# electronicload.net
KiCad netlist of a schematic drawn in EAGLE
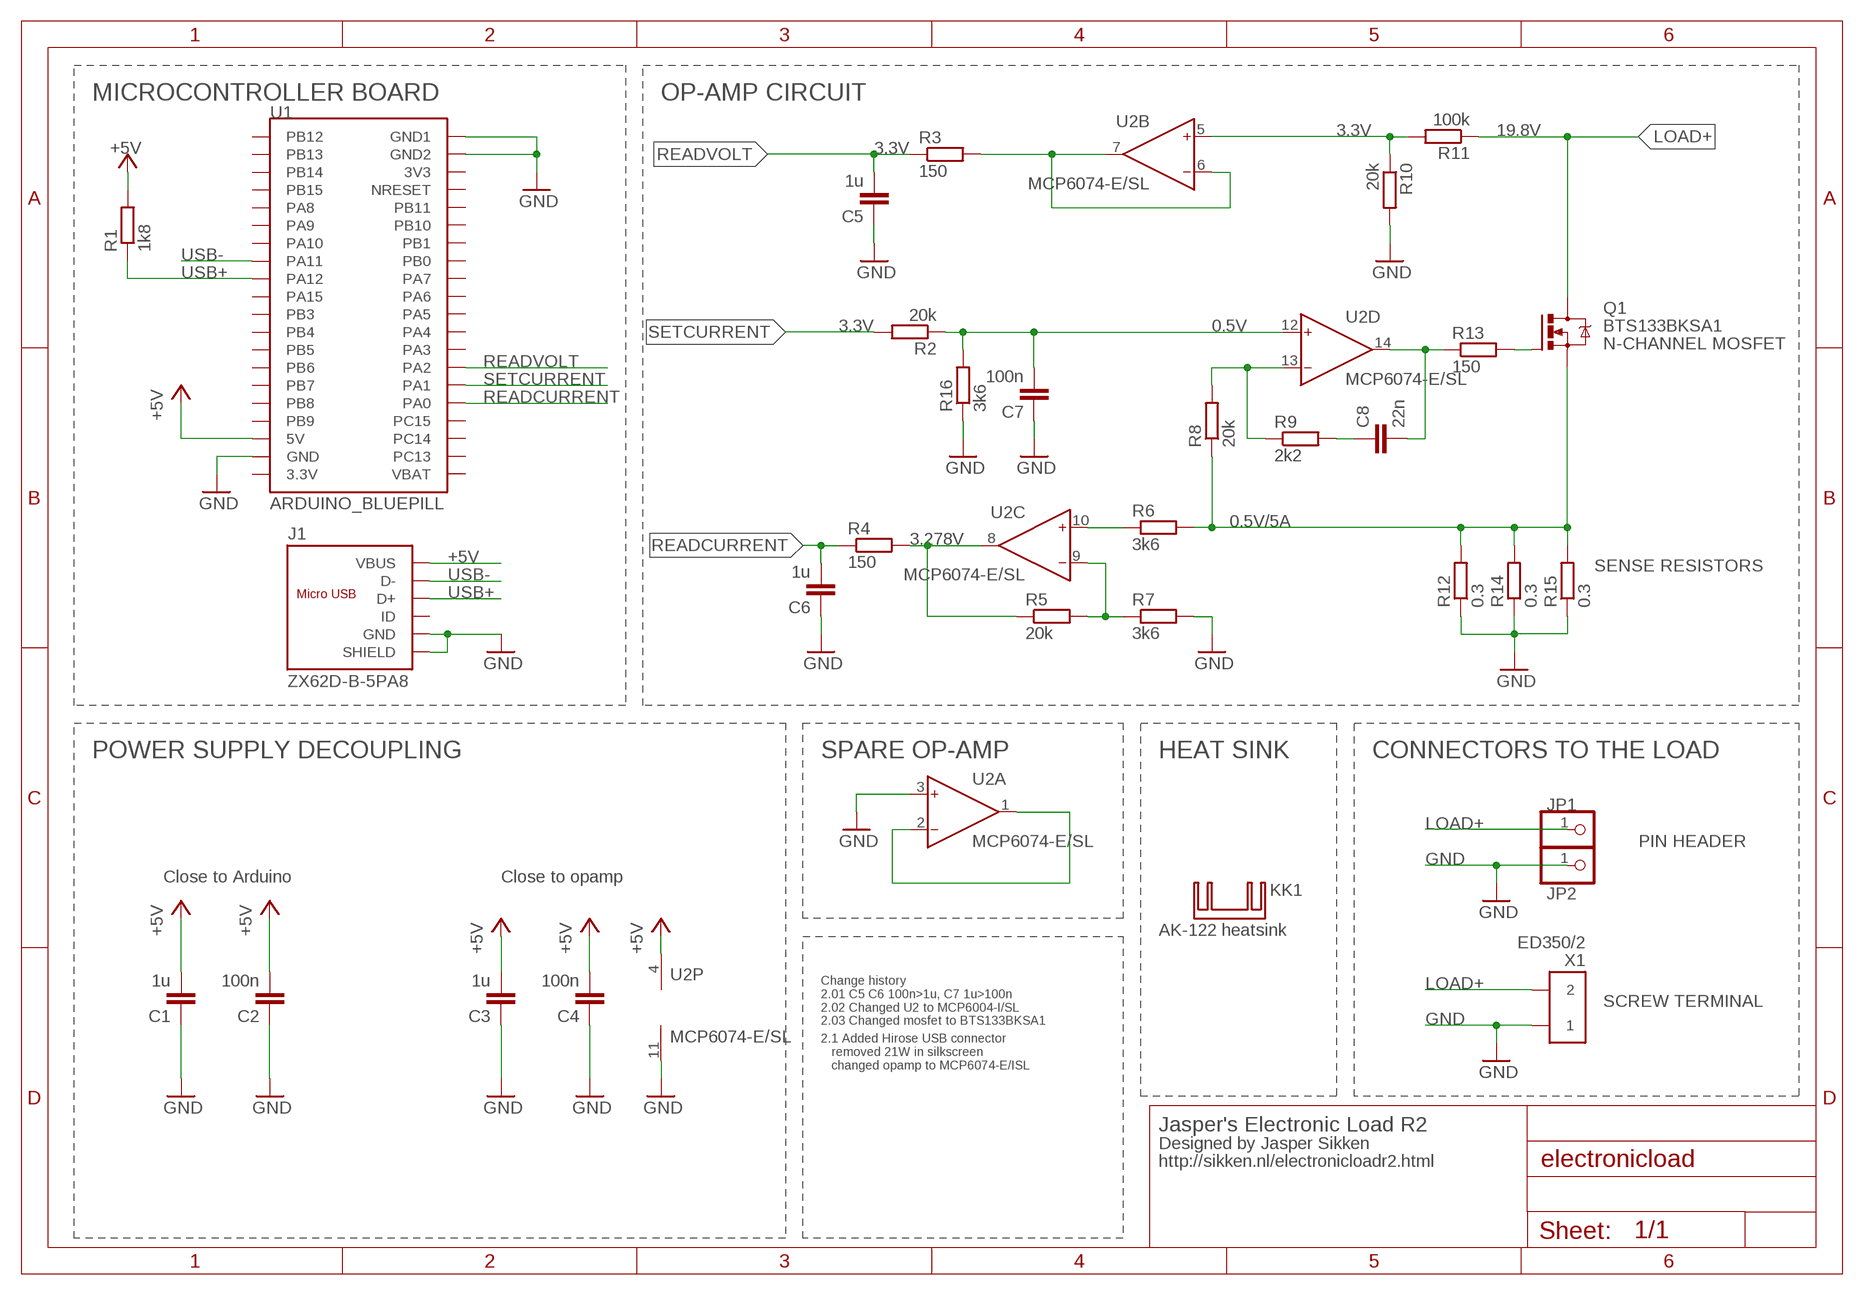
[diagram p0: schematic, sheet 1]

(export (version "E")
  (design (tool "Eeschema 10.0.6"))
  (components
    (comp (ref "C1")
      (value "1u")
      (footprint "eagle-import:C0603K")
      (fields (field (name "TOLERANCE") "10%") (field (name "VOLTAGE") "16V"))
      (libsource (lib "eagle-import") (part "C-EUC0603K"))
    )
    (comp (ref "C2")
      (value "100n")
      (footprint "eagle-import:C0603K")
      (fields (field (name "TOLERANCE") "10%") (field (name "VOLTAGE") "50V"))
      (libsource (lib "eagle-import") (part "C-EUC0603K"))
    )
    (comp (ref "C3")
      (value "1u")
      (footprint "eagle-import:C0603K")
      (fields (field (name "TOLERANCE") "10%") (field (name "VOLTAGE") "16V"))
      (libsource (lib "eagle-import") (part "C-EUC0603K"))
    )
    (comp (ref "C4")
      (value "100n")
      (footprint "eagle-import:C0603K")
      (fields (field (name "TOLERANCE") "10%") (field (name "VOLTAGE") "50V"))
      (libsource (lib "eagle-import") (part "C-EUC0603K"))
    )
    (comp (ref "C5")
      (value "1u")
      (footprint "eagle-import:C0603K")
      (fields (field (name "TOLERANCE") "10%") (field (name "VOLTAGE") "50V"))
      (libsource (lib "eagle-import") (part "C-EUC0603K"))
    )
    (comp (ref "C6")
      (value "1u")
      (footprint "eagle-import:C0603K")
      (fields (field (name "TOLERANCE") "10%") (field (name "VOLTAGE") "50V"))
      (libsource (lib "eagle-import") (part "C-EUC0603K"))
    )
    (comp (ref "C7")
      (value "100n")
      (footprint "eagle-import:C0603K")
      (fields (field (name "TOLERANCE") "10%") (field (name "VOLTAGE") "50V"))
      (libsource (lib "eagle-import") (part "C-EUC0603K"))
    )
    (comp (ref "C8")
      (value "22n")
      (footprint "eagle-import:C0603K")
      (fields (field (name "TOLERANCE") "10%") (field (name "VOLTAGE") "25V"))
      (libsource (lib "eagle-import") (part "C-EUC0603K"))
    )
    (comp (ref "J1")
      (value "ZX62D-B-5PA8")
      (footprint "eagle-import:MICRO-USB5+6P-SMD-0.65-AB")
      (fields (field (name "MF") "Hirose"))
      (libsource (lib "eagle-import") (part "MICRO-USB-SMD"))
    )
    (comp (ref "JP1")
      (value "PINHD-1X1")
      (footprint "eagle-import:1X01")
      (libsource (lib "eagle-import") (part "PINHD-1X1"))
    )
    (comp (ref "JP2")
      (value "PINHD-1X1")
      (footprint "eagle-import:1X01")
      (libsource (lib "eagle-import") (part "PINHD-1X1"))
    )
    (comp (ref "KK1")
      (value "SK129")
      (footprint "eagle-import:SK129-HOLE")
      (libsource (lib "eagle-import") (part "SK129"))
    )
    (comp (ref "Q1")
      (value "BTS133BKSA1")
      (footprint "eagle-import:TO220BV")
      (fields (field (name "DIGIKEY") "BTS133BKSA1-ND"))
      (libsource (lib "eagle-import") (part "IRLZ44Z"))
    )
    (comp (ref "R1")
      (value "1k8")
      (footprint "eagle-import:R0603")
      (libsource (lib "eagle-import") (part "R-EU_R0603"))
    )
    (comp (ref "R2")
      (value "20k")
      (footprint "eagle-import:R0603")
      (libsource (lib "eagle-import") (part "R-EU_R0603"))
    )
    (comp (ref "R3")
      (value "150")
      (footprint "eagle-import:R0603")
      (libsource (lib "eagle-import") (part "R-EU_R0603"))
    )
    (comp (ref "R4")
      (value "150")
      (footprint "eagle-import:R0603")
      (libsource (lib "eagle-import") (part "R-EU_R0603"))
    )
    (comp (ref "R5")
      (value "20k")
      (footprint "eagle-import:R0603")
      (libsource (lib "eagle-import") (part "R-EU_R0603"))
    )
    (comp (ref "R6")
      (value "3k6")
      (footprint "eagle-import:R0603")
      (libsource (lib "eagle-import") (part "R-EU_R0603"))
    )
    (comp (ref "R7")
      (value "3k6")
      (footprint "eagle-import:R0603")
      (libsource (lib "eagle-import") (part "R-EU_R0603"))
    )
    (comp (ref "R8")
      (value "20k")
      (footprint "eagle-import:R0603")
      (libsource (lib "eagle-import") (part "R-EU_R0603"))
    )
    (comp (ref "R9")
      (value "2k2")
      (footprint "eagle-import:R0603")
      (libsource (lib "eagle-import") (part "R-EU_R0603"))
    )
    (comp (ref "R10")
      (value "20k")
      (footprint "eagle-import:R0603")
      (libsource (lib "eagle-import") (part "R-EU_R0603"))
    )
    (comp (ref "R11")
      (value "100k")
      (footprint "eagle-import:R0603")
      (libsource (lib "eagle-import") (part "R-EU_R0603"))
    )
    (comp (ref "R12")
      (value "0.3")
      (footprint "eagle-import:R2512")
      (libsource (lib "eagle-import") (part "R2512_10R"))
    )
    (comp (ref "R13")
      (value "150")
      (footprint "eagle-import:R0603")
      (libsource (lib "eagle-import") (part "R-EU_R0603"))
    )
    (comp (ref "R14")
      (value "0.3")
      (footprint "eagle-import:R2512")
      (libsource (lib "eagle-import") (part "R2512_10R"))
    )
    (comp (ref "R15")
      (value "0.3")
      (footprint "eagle-import:R2512")
      (libsource (lib "eagle-import") (part "R2512_10R"))
    )
    (comp (ref "R16")
      (value "3k6")
      (footprint "eagle-import:R0603")
      (libsource (lib "eagle-import") (part "R-EU_R0603"))
    )
    (comp (ref "U1")
      (value "ARDUINO_BLUEPILL")
      (footprint "eagle-import:ARDUINO_BLUEPILL")
      (libsource (lib "eagle-import") (part "ARDUINO_BLUEPILL"))
    )
    (comp (ref "U2")
      (value "MCP6074-E/SL")
      (footprint "eagle-import:SO14")
      (libsource (lib "eagle-import") (part "AD8608R"))
    )
    (comp (ref "X1")
      (value "ED350/2")
      (footprint "eagle-import:ED350_2")
      (libsource (lib "eagle-import") (part "ED350/2"))
    )
  )
  (nets
    (net (code "1") (name "+5V") (class "Default")
      (node (ref "C1") (pin "2") (pinfunction "2_2") (pintype "passive"))
      (node (ref "C2") (pin "2") (pinfunction "2_2") (pintype "passive"))
      (node (ref "C3") (pin "2") (pinfunction "2_2") (pintype "passive"))
      (node (ref "C4") (pin "2") (pinfunction "2_2") (pintype "passive"))
      (node (ref "J1") (pin "1") (pinfunction "VBUS_1") (pintype "power_in"))
      (node (ref "R1") (pin "2") (pinfunction "2_2") (pintype "passive"))
      (node (ref "U1") (pin "P$37") (pinfunction "5V_P$37") (pintype "bidirectional"))
      (node (ref "U2") (pin "4") (pinfunction "V+_4") (pintype "power_in"))
    )
    (net (code "2") (name "/USB+") (class "Default")
      (node (ref "J1") (pin "3") (pinfunction "D+_3") (pintype "bidirectional"))
      (node (ref "R1") (pin "1") (pinfunction "1_1") (pintype "passive"))
      (node (ref "U1") (pin "P$28") (pinfunction "PA12_P$28") (pintype "bidirectional"))
    )
    (net (code "3") (name "/USB-") (class "Default")
      (node (ref "J1") (pin "2") (pinfunction "D-_2") (pintype "bidirectional"))
      (node (ref "U1") (pin "P$27") (pinfunction "PA11_P$27") (pintype "bidirectional"))
    )
    (net (code "4") (name "GND") (class "Default")
      (node (ref "C1") (pin "1") (pinfunction "1_1") (pintype "passive"))
      (node (ref "C2") (pin "1") (pinfunction "1_1") (pintype "passive"))
      (node (ref "C3") (pin "1") (pinfunction "1_1") (pintype "passive"))
      (node (ref "C4") (pin "1") (pinfunction "1_1") (pintype "passive"))
      (node (ref "C5") (pin "1") (pinfunction "1_1") (pintype "passive"))
      (node (ref "C6") (pin "1") (pinfunction "1_1") (pintype "passive"))
      (node (ref "C7") (pin "1") (pinfunction "1_1") (pintype "passive"))
      (node (ref "J1") (pin "5") (pinfunction "GND_5") (pintype "power_in"))
      (node (ref "J1") (pin "P1") (pinfunction "SHIELD_P1") (pintype "power_in"))
      (node (ref "J1") (pin "P2") (pinfunction "SHIELD_P2") (pintype "power_in"))
      (node (ref "J1") (pin "P3") (pinfunction "SHIELD_P3") (pintype "power_in"))
      (node (ref "J1") (pin "P4") (pinfunction "SHIELD_P4") (pintype "power_in"))
      (node (ref "J1") (pin "P5") (pinfunction "SHIELD_P5") (pintype "power_in"))
      (node (ref "J1") (pin "P6") (pinfunction "SHIELD_P6") (pintype "power_in"))
      (node (ref "JP2") (pin "1") (pinfunction "1_1") (pintype "passive"))
      (node (ref "R10") (pin "2") (pinfunction "2_2") (pintype "passive"))
      (node (ref "R12") (pin "1") (pinfunction "1_1") (pintype "passive"))
      (node (ref "R14") (pin "1") (pinfunction "1_1") (pintype "passive"))
      (node (ref "R15") (pin "1") (pinfunction "1_1") (pintype "passive"))
      (node (ref "R16") (pin "1") (pinfunction "1_1") (pintype "passive"))
      (node (ref "R7") (pin "2") (pinfunction "2_2") (pintype "passive"))
      (node (ref "U1") (pin "P$18") (pinfunction "GND2_P$18") (pintype "bidirectional"))
      (node (ref "U1") (pin "P$19") (pinfunction "GND1_P$19") (pintype "bidirectional"))
      (node (ref "U1") (pin "P$38") (pinfunction "GND_P$38") (pintype "bidirectional"))
      (node (ref "U2") (pin "11") (pinfunction "V-_11") (pintype "power_in"))
      (node (ref "U2") (pin "3") (pinfunction "IN+_3") (pintype "input"))
      (node (ref "X1") (pin "P$1") (pinfunction "1_P$1") (pintype "bidirectional"))
    )
    (net (code "5") (name "LOAD+") (class "Default")
      (node (ref "JP1") (pin "1") (pinfunction "1_1") (pintype "passive"))
      (node (ref "Q1") (pin "D") (pinfunction "D_D") (pintype "passive"))
      (node (ref "R11") (pin "1") (pinfunction "1_1") (pintype "passive"))
      (node (ref "X1") (pin "P$2") (pinfunction "2_P$2") (pintype "bidirectional"))
    )
    (net (code "6") (name "Net-(C8-Pad1)") (class "Default")
      (node (ref "C8") (pin "1") (pinfunction "1_1") (pintype "passive"))
      (node (ref "R9") (pin "2") (pinfunction "2_2") (pintype "passive"))
    )
    (net (code "7") (name "Net-(Q1-PadG)") (class "Default")
      (node (ref "Q1") (pin "G") (pinfunction "G_G") (pintype "passive"))
      (node (ref "R13") (pin "2") (pinfunction "2_2") (pintype "passive"))
    )
    (net (code "8") (name "Net-(Q1-PadS)") (class "Default")
      (node (ref "Q1") (pin "S") (pinfunction "S_S") (pintype "passive"))
      (node (ref "R12") (pin "2") (pinfunction "2_2") (pintype "passive"))
      (node (ref "R14") (pin "2") (pinfunction "2_2") (pintype "passive"))
      (node (ref "R15") (pin "2") (pinfunction "2_2") (pintype "passive"))
      (node (ref "R6") (pin "2") (pinfunction "2_2") (pintype "passive"))
      (node (ref "R8") (pin "1") (pinfunction "1_1") (pintype "passive"))
    )
    (net (code "9") (name "Net-(U2A-IN-)") (class "Default")
      (node (ref "U2") (pin "1") (pinfunction "OUT_1") (pintype "output"))
      (node (ref "U2") (pin "2") (pinfunction "IN-_2") (pintype "input"))
    )
    (net (code "10") (name "Net-(U2B-IN+)") (class "Default")
      (node (ref "R10") (pin "1") (pinfunction "1_1") (pintype "passive"))
      (node (ref "R11") (pin "2") (pinfunction "2_2") (pintype "passive"))
      (node (ref "U2") (pin "5") (pinfunction "IN+_5") (pintype "input"))
    )
    (net (code "11") (name "Net-(U2B-IN-)") (class "Default")
      (node (ref "R3") (pin "2") (pinfunction "2_2") (pintype "passive"))
      (node (ref "U2") (pin "6") (pinfunction "IN-_6") (pintype "input"))
      (node (ref "U2") (pin "7") (pinfunction "OUT_7") (pintype "output"))
    )
    (net (code "12") (name "Net-(U2C-IN+)") (class "Default")
      (node (ref "R6") (pin "1") (pinfunction "1_1") (pintype "passive"))
      (node (ref "U2") (pin "10") (pinfunction "IN+_10") (pintype "input"))
    )
    (net (code "13") (name "Net-(U2C-IN-)") (class "Default")
      (node (ref "R5") (pin "2") (pinfunction "2_2") (pintype "passive"))
      (node (ref "R7") (pin "1") (pinfunction "1_1") (pintype "passive"))
      (node (ref "U2") (pin "9") (pinfunction "IN-_9") (pintype "input"))
    )
    (net (code "14") (name "Net-(U2C-OUT)") (class "Default")
      (node (ref "R4") (pin "2") (pinfunction "2_2") (pintype "passive"))
      (node (ref "R5") (pin "1") (pinfunction "1_1") (pintype "passive"))
      (node (ref "U2") (pin "8") (pinfunction "OUT_8") (pintype "output"))
    )
    (net (code "15") (name "Net-(U2D-IN+)") (class "Default")
      (node (ref "C7") (pin "2") (pinfunction "2_2") (pintype "passive"))
      (node (ref "R16") (pin "2") (pinfunction "2_2") (pintype "passive"))
      (node (ref "R2") (pin "1") (pinfunction "1_1") (pintype "passive"))
      (node (ref "U2") (pin "12") (pinfunction "IN+_12") (pintype "input"))
    )
    (net (code "16") (name "Net-(U2D-IN-)") (class "Default")
      (node (ref "R8") (pin "2") (pinfunction "2_2") (pintype "passive"))
      (node (ref "R9") (pin "1") (pinfunction "1_1") (pintype "passive"))
      (node (ref "U2") (pin "13") (pinfunction "IN-_13") (pintype "input"))
    )
    (net (code "17") (name "Net-(U2D-OUT)") (class "Default")
      (node (ref "C8") (pin "2") (pinfunction "2_2") (pintype "passive"))
      (node (ref "R13") (pin "1") (pinfunction "1_1") (pintype "passive"))
      (node (ref "U2") (pin "14") (pinfunction "OUT_14") (pintype "output"))
    )
    (net (code "18") (name "READCURRENT") (class "Default")
      (node (ref "C6") (pin "2") (pinfunction "2_2") (pintype "passive"))
      (node (ref "R4") (pin "1") (pinfunction "1_1") (pintype "passive"))
      (node (ref "U1") (pin "P$4") (pinfunction "PA0_P$4") (pintype "bidirectional"))
    )
    (net (code "19") (name "READVOLT") (class "Default")
      (node (ref "C5") (pin "2") (pinfunction "2_2") (pintype "passive"))
      (node (ref "R3") (pin "1") (pinfunction "1_1") (pintype "passive"))
      (node (ref "U1") (pin "P$6") (pinfunction "PA2_P$6") (pintype "bidirectional"))
    )
    (net (code "20") (name "SETCURRENT") (class "Default")
      (node (ref "R2") (pin "2") (pinfunction "2_2") (pintype "passive"))
      (node (ref "U1") (pin "P$5") (pinfunction "PA1_P$5") (pintype "bidirectional"))
    )
    (net (code "21") (name "unconnected-(J1-ID-Pad4)") (class "Default")
      (node (ref "J1") (pin "4") (pinfunction "ID_4") (pintype "bidirectional"))
    )
    (net (code "22") (name "unconnected-(U1-3.3V-PadP$39)") (class "Default")
      (node (ref "U1") (pin "P$39") (pinfunction "3.3V_P$39") (pintype "bidirectional"))
    )
    (net (code "23") (name "unconnected-(U1-3V3-PadP$17)") (class "Default")
      (node (ref "U1") (pin "P$17") (pinfunction "3V3_P$17") (pintype "bidirectional"))
    )
    (net (code "24") (name "unconnected-(U1-NRESET-PadP$16)") (class "Default")
      (node (ref "U1") (pin "P$16") (pinfunction "NRESET_P$16") (pintype "bidirectional"))
    )
    (net (code "25") (name "unconnected-(U1-PA3-PadP$7)") (class "Default")
      (node (ref "U1") (pin "P$7") (pinfunction "PA3_P$7") (pintype "bidirectional"))
    )
    (net (code "26") (name "unconnected-(U1-PA4-PadP$8)") (class "Default")
      (node (ref "U1") (pin "P$8") (pinfunction "PA4_P$8") (pintype "bidirectional"))
    )
    (net (code "27") (name "unconnected-(U1-PA5-PadP$9)") (class "Default")
      (node (ref "U1") (pin "P$9") (pinfunction "PA5_P$9") (pintype "bidirectional"))
    )
    (net (code "28") (name "unconnected-(U1-PA6-PadP$10)") (class "Default")
      (node (ref "U1") (pin "P$10") (pinfunction "PA6_P$10") (pintype "bidirectional"))
    )
    (net (code "29") (name "unconnected-(U1-PA7-PadP$11)") (class "Default")
      (node (ref "U1") (pin "P$11") (pinfunction "PA7_P$11") (pintype "bidirectional"))
    )
    (net (code "30") (name "unconnected-(U1-PA8-PadP$24)") (class "Default")
      (node (ref "U1") (pin "P$24") (pinfunction "PA8_P$24") (pintype "bidirectional"))
    )
    (net (code "31") (name "unconnected-(U1-PA9-PadP$25)") (class "Default")
      (node (ref "U1") (pin "P$25") (pinfunction "PA9_P$25") (pintype "bidirectional"))
    )
    (net (code "32") (name "unconnected-(U1-PA10-PadP$26)") (class "Default")
      (node (ref "U1") (pin "P$26") (pinfunction "PA10_P$26") (pintype "bidirectional"))
    )
    (net (code "33") (name "unconnected-(U1-PA15-PadP$29)") (class "Default")
      (node (ref "U1") (pin "P$29") (pinfunction "PA15_P$29") (pintype "bidirectional"))
    )
    (net (code "34") (name "unconnected-(U1-PB0-PadP$12)") (class "Default")
      (node (ref "U1") (pin "P$12") (pinfunction "PB0_P$12") (pintype "bidirectional"))
    )
    (net (code "35") (name "unconnected-(U1-PB1-PadP$13)") (class "Default")
      (node (ref "U1") (pin "P$13") (pinfunction "PB1_P$13") (pintype "bidirectional"))
    )
    (net (code "36") (name "unconnected-(U1-PB3-PadP$30)") (class "Default")
      (node (ref "U1") (pin "P$30") (pinfunction "PB3_P$30") (pintype "bidirectional"))
    )
    (net (code "37") (name "unconnected-(U1-PB4-PadP$31)") (class "Default")
      (node (ref "U1") (pin "P$31") (pinfunction "PB4_P$31") (pintype "bidirectional"))
    )
    (net (code "38") (name "unconnected-(U1-PB5-PadP$32)") (class "Default")
      (node (ref "U1") (pin "P$32") (pinfunction "PB5_P$32") (pintype "bidirectional"))
    )
    (net (code "39") (name "unconnected-(U1-PB6-PadP$33)") (class "Default")
      (node (ref "U1") (pin "P$33") (pinfunction "PB6_P$33") (pintype "bidirectional"))
    )
    (net (code "40") (name "unconnected-(U1-PB7-PadP$34)") (class "Default")
      (node (ref "U1") (pin "P$34") (pinfunction "PB7_P$34") (pintype "bidirectional"))
    )
    (net (code "41") (name "unconnected-(U1-PB8-PadP$35)") (class "Default")
      (node (ref "U1") (pin "P$35") (pinfunction "PB8_P$35") (pintype "bidirectional"))
    )
    (net (code "42") (name "unconnected-(U1-PB9-PadP$36)") (class "Default")
      (node (ref "U1") (pin "P$36") (pinfunction "PB9_P$36") (pintype "bidirectional"))
    )
    (net (code "43") (name "unconnected-(U1-PB10-PadP$14)") (class "Default")
      (node (ref "U1") (pin "P$14") (pinfunction "PB10_P$14") (pintype "bidirectional"))
    )
    (net (code "44") (name "unconnected-(U1-PB11-PadP$15)") (class "Default")
      (node (ref "U1") (pin "P$15") (pinfunction "PB11_P$15") (pintype "bidirectional"))
    )
    (net (code "45") (name "unconnected-(U1-PB12-PadP$20)") (class "Default")
      (node (ref "U1") (pin "P$20") (pinfunction "PB12_P$20") (pintype "bidirectional"))
    )
    (net (code "46") (name "unconnected-(U1-PB13-PadP$21)") (class "Default")
      (node (ref "U1") (pin "P$21") (pinfunction "PB13_P$21") (pintype "bidirectional"))
    )
    (net (code "47") (name "unconnected-(U1-PB14-PadP$22)") (class "Default")
      (node (ref "U1") (pin "P$22") (pinfunction "PB14_P$22") (pintype "bidirectional"))
    )
    (net (code "48") (name "unconnected-(U1-PB15-PadP$23)") (class "Default")
      (node (ref "U1") (pin "P$23") (pinfunction "PB15_P$23") (pintype "bidirectional"))
    )
    (net (code "49") (name "unconnected-(U1-PC13-PadP$1)") (class "Default")
      (node (ref "U1") (pin "P$1") (pinfunction "PC13_P$1") (pintype "bidirectional"))
    )
    (net (code "50") (name "unconnected-(U1-PC14-PadP$2)") (class "Default")
      (node (ref "U1") (pin "P$2") (pinfunction "PC14_P$2") (pintype "bidirectional"))
    )
    (net (code "51") (name "unconnected-(U1-PC15-PadP$3)") (class "Default")
      (node (ref "U1") (pin "P$3") (pinfunction "PC15_P$3") (pintype "bidirectional"))
    )
    (net (code "52") (name "unconnected-(U1-VBAT-PadP$0)") (class "Default")
      (node (ref "U1") (pin "P$0") (pinfunction "VBAT_P$0") (pintype "bidirectional"))
    )
  )
)
